# Sheet1.net
KiCad netlist of a schematic drawn in Altium Designer
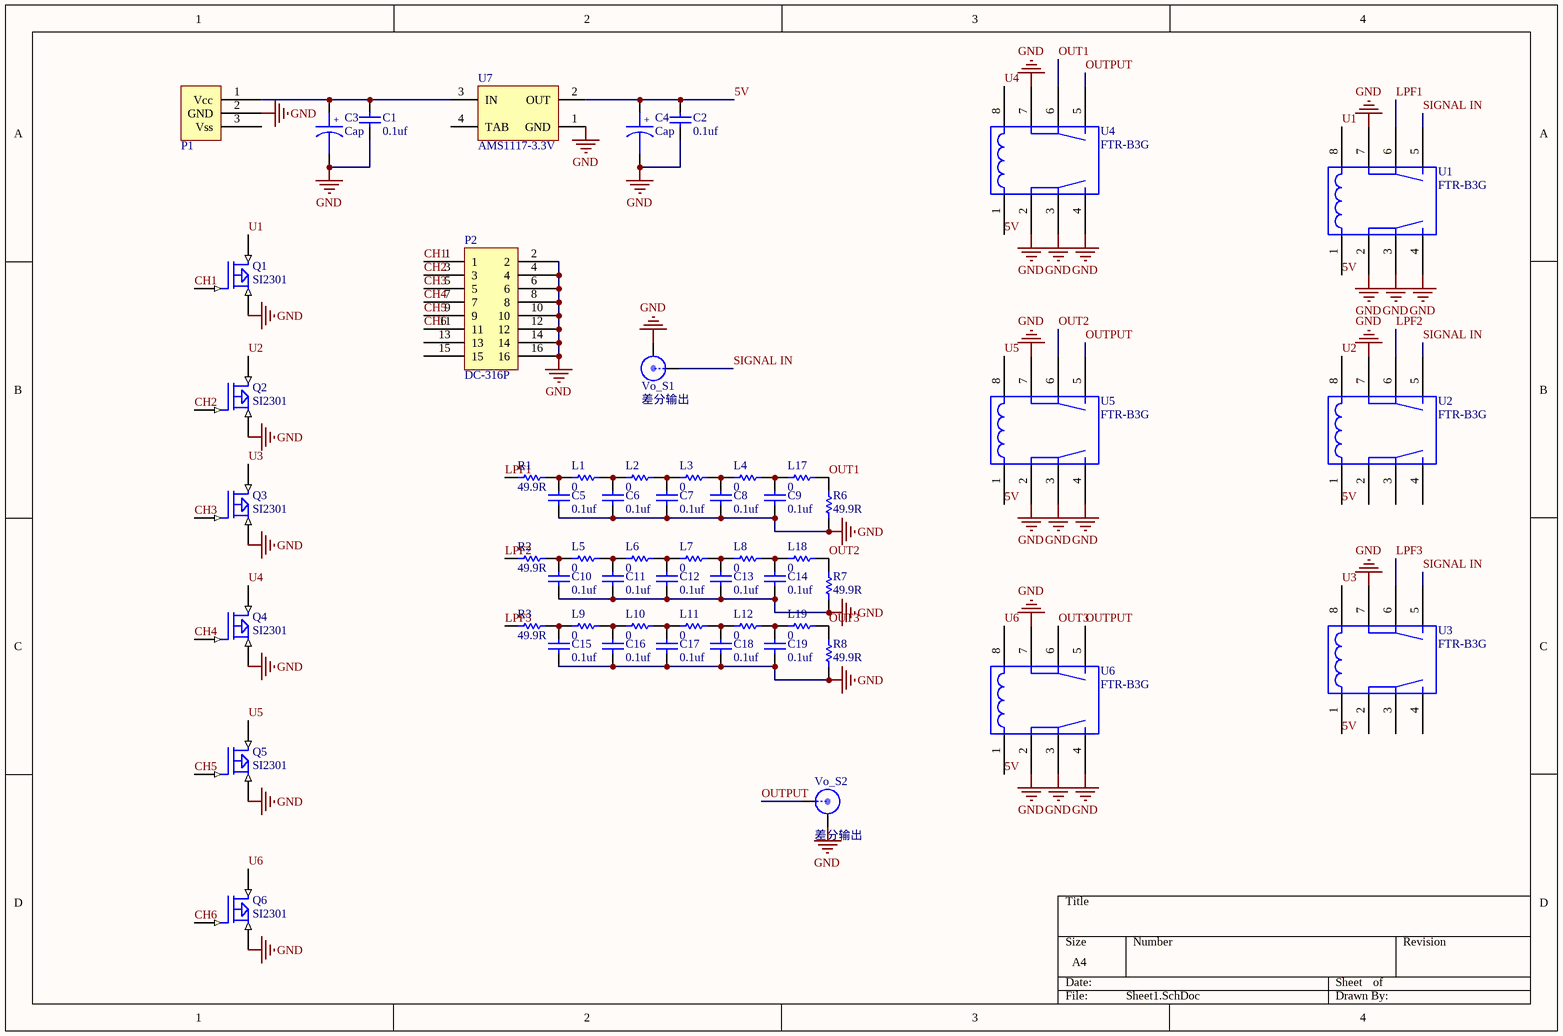
[diagram p0: Sheet1.SchDoc]

(export (version "E")
  (design (tool "Eeschema 10.0.6"))
  (components
    (comp (ref "C1") (value "0.1uf") (footprint "0805") (libsource (lib "Schlib1") (part "Cap")))
    (comp (ref "C2") (value "0.1uf") (footprint "0805") (libsource (lib "Schlib1") (part "Cap")))
    (comp (ref "C3")
      (value "Cap")
      (footprint "3216C-TYPE_A")
      (libsource (lib "Schlib1") (part "Tantalium Cap"))
    )
    (comp (ref "C4")
      (value "Cap")
      (footprint "3216C-TYPE_A")
      (libsource (lib "Schlib1") (part "Tantalium Cap"))
    )
    (comp (ref "C5") (value "0.1uf") (footprint "0603C") (libsource (lib "Schlib1") (part "Cap")))
    (comp (ref "C6") (value "0.1uf") (footprint "0603C") (libsource (lib "Schlib1") (part "Cap")))
    (comp (ref "C7") (value "0.1uf") (footprint "0603C") (libsource (lib "Schlib1") (part "Cap")))
    (comp (ref "C8") (value "0.1uf") (footprint "0603C") (libsource (lib "Schlib1") (part "Cap")))
    (comp (ref "C9") (value "0.1uf") (footprint "0603C") (libsource (lib "Schlib1") (part "Cap")))
    (comp (ref "C10") (value "0.1uf") (footprint "0603C") (libsource (lib "Schlib1") (part "Cap")))
    (comp (ref "C11") (value "0.1uf") (footprint "0603C") (libsource (lib "Schlib1") (part "Cap")))
    (comp (ref "C12") (value "0.1uf") (footprint "0603C") (libsource (lib "Schlib1") (part "Cap")))
    (comp (ref "C13") (value "0.1uf") (footprint "0603C") (libsource (lib "Schlib1") (part "Cap")))
    (comp (ref "C14") (value "0.1uf") (footprint "0603C") (libsource (lib "Schlib1") (part "Cap")))
    (comp (ref "C15") (value "0.1uf") (footprint "0603C") (libsource (lib "Schlib1") (part "Cap")))
    (comp (ref "C16") (value "0.1uf") (footprint "0603C") (libsource (lib "Schlib1") (part "Cap")))
    (comp (ref "C17") (value "0.1uf") (footprint "0603C") (libsource (lib "Schlib1") (part "Cap")))
    (comp (ref "C18") (value "0.1uf") (footprint "0603C") (libsource (lib "Schlib1") (part "Cap")))
    (comp (ref "C19") (value "0.1uf") (footprint "0603C") (libsource (lib "Schlib1") (part "Cap")))
    (comp (ref "L1") (value "0") (footprint "0603R") (libsource (lib "Schlib1") (part "Res")))
    (comp (ref "L2") (value "0") (footprint "0603R") (libsource (lib "Schlib1") (part "Res")))
    (comp (ref "L3") (value "0") (footprint "0603R") (libsource (lib "Schlib1") (part "Res")))
    (comp (ref "L4") (value "0") (footprint "0603R") (libsource (lib "Schlib1") (part "Res")))
    (comp (ref "L5") (value "0") (footprint "0603R") (libsource (lib "Schlib1") (part "Res")))
    (comp (ref "L6") (value "0") (footprint "0603R") (libsource (lib "Schlib1") (part "Res")))
    (comp (ref "L7") (value "0") (footprint "0603R") (libsource (lib "Schlib1") (part "Res")))
    (comp (ref "L8") (value "0") (footprint "0603R") (libsource (lib "Schlib1") (part "Res")))
    (comp (ref "L9") (value "0") (footprint "0603R") (libsource (lib "Schlib1") (part "Res")))
    (comp (ref "L10") (value "0") (footprint "0603R") (libsource (lib "Schlib1") (part "Res")))
    (comp (ref "L11") (value "0") (footprint "0603R") (libsource (lib "Schlib1") (part "Res")))
    (comp (ref "L12") (value "0") (footprint "0603R") (libsource (lib "Schlib1") (part "Res")))
    (comp (ref "L17") (value "0") (footprint "0603R") (libsource (lib "Schlib1") (part "Res")))
    (comp (ref "L18") (value "0") (footprint "0603R") (libsource (lib "Schlib1") (part "Res")))
    (comp (ref "L19") (value "0") (footprint "0603R") (libsource (lib "Schlib1") (part "Res")))
    (comp (ref "P1")
      (value "XH2.54-3p")
      (footprint "XH2.54-3p")
      (libsource (lib "Schlib1") (part "XH2.54-3p"))
    )
    (comp (ref "P2") (value "DC-316P") (footprint "DC3-14P") (libsource (lib "Schlib1") (part "DC3-16P")))
    (comp (ref "Q1") (value "SI2301") (footprint "SOT-23") (libsource (lib "Schlib1") (part "SI2301")))
    (comp (ref "Q2") (value "SI2301") (footprint "SOT-23") (libsource (lib "Schlib1") (part "SI2301")))
    (comp (ref "Q3") (value "SI2301") (footprint "SOT-23") (libsource (lib "Schlib1") (part "SI2301")))
    (comp (ref "Q4") (value "SI2301") (footprint "SOT-23") (libsource (lib "Schlib1") (part "SI2301")))
    (comp (ref "Q5") (value "SI2301") (footprint "SOT-23") (libsource (lib "Schlib1") (part "SI2301")))
    (comp (ref "Q6") (value "SI2301") (footprint "SOT-23") (libsource (lib "Schlib1") (part "SI2301")))
    (comp (ref "R1") (value "49.9R") (footprint "0603R") (libsource (lib "Schlib1") (part "Res")))
    (comp (ref "R2") (value "49.9R") (footprint "0603R") (libsource (lib "Schlib1") (part "Res")))
    (comp (ref "R3") (value "49.9R") (footprint "0603R") (libsource (lib "Schlib1") (part "Res")))
    (comp (ref "R6") (value "49.9R") (footprint "0603R") (libsource (lib "Schlib1") (part "Res")))
    (comp (ref "R7") (value "49.9R") (footprint "0603R") (libsource (lib "Schlib1") (part "Res")))
    (comp (ref "R8") (value "49.9R") (footprint "0603R") (libsource (lib "Schlib1") (part "Res")))
    (comp (ref "U1") (value "FTR-B3G") (footprint "FTR-B3G") (libsource (lib "Schlib1") (part "FTR-B3G")))
    (comp (ref "U2") (value "FTR-B3G") (footprint "FTR-B3G") (libsource (lib "Schlib1") (part "FTR-B3G")))
    (comp (ref "U3") (value "FTR-B3G") (footprint "FTR-B3G") (libsource (lib "Schlib1") (part "FTR-B3G")))
    (comp (ref "U4") (value "FTR-B3G") (footprint "FTR-B3G") (libsource (lib "Schlib1") (part "FTR-B3G")))
    (comp (ref "U5") (value "FTR-B3G") (footprint "FTR-B3G") (libsource (lib "Schlib1") (part "FTR-B3G")))
    (comp (ref "U6") (value "FTR-B3G") (footprint "FTR-B3G") (libsource (lib "Schlib1") (part "FTR-B3G")))
    (comp (ref "U7")
      (value "AMS1117-3.3V")
      (footprint "SOT-223")
      (libsource (lib "Schlib1") (part "AMS1117-3.3V"))
    )
    (comp (ref "Vo_S1") (value "差分输出") (footprint "SMA-LYING") (libsource (lib "Schlib1") (part "SMA")))
    (comp (ref "Vo_S2") (value "差分输出") (footprint "SMA-LYING") (libsource (lib "Schlib1") (part "SMA")))
  )
  (nets
    (net (code "1") (name "/5V") (class "Default")
      (node (ref "C2") (pin "2") (pinfunction "2_2") (pintype "passive"))
      (node (ref "C4") (pin "1") (pinfunction "1_1") (pintype "passive"))
      (node (ref "U1") (pin "1") (pinfunction "1_1") (pintype "passive"))
      (node (ref "U2") (pin "1") (pinfunction "1_1") (pintype "passive"))
      (node (ref "U3") (pin "1") (pinfunction "1_1") (pintype "passive"))
      (node (ref "U4") (pin "1") (pinfunction "1_1") (pintype "passive"))
      (node (ref "U5") (pin "1") (pinfunction "1_1") (pintype "passive"))
      (node (ref "U6") (pin "1") (pinfunction "1_1") (pintype "passive"))
      (node (ref "U7") (pin "2") (pinfunction "OUT_2") (pintype "power_in"))
    )
    (net (code "2") (name "/CH1") (class "Default")
      (node (ref "P2") (pin "1") (pinfunction "1_1") (pintype "passive"))
      (node (ref "Q1") (pin "1") (pinfunction "G_1") (pintype "input"))
    )
    (net (code "3") (name "/CH2") (class "Default")
      (node (ref "P2") (pin "3") (pinfunction "3_3") (pintype "passive"))
      (node (ref "Q2") (pin "1") (pinfunction "G_1") (pintype "input"))
    )
    (net (code "4") (name "/CH3") (class "Default")
      (node (ref "P2") (pin "5") (pinfunction "5_5") (pintype "passive"))
      (node (ref "Q3") (pin "1") (pinfunction "G_1") (pintype "input"))
    )
    (net (code "5") (name "/CH4") (class "Default")
      (node (ref "P2") (pin "7") (pinfunction "7_7") (pintype "passive"))
      (node (ref "Q4") (pin "1") (pinfunction "G_1") (pintype "input"))
    )
    (net (code "6") (name "/CH5") (class "Default")
      (node (ref "P2") (pin "9") (pinfunction "9_9") (pintype "passive"))
      (node (ref "Q5") (pin "1") (pinfunction "G_1") (pintype "input"))
    )
    (net (code "7") (name "/CH6") (class "Default")
      (node (ref "P2") (pin "11") (pinfunction "11_11") (pintype "passive"))
      (node (ref "Q6") (pin "1") (pinfunction "G_1") (pintype "input"))
    )
    (net (code "8") (name "/LPF1") (class "Default")
      (node (ref "R1") (pin "1") (pinfunction "1_1") (pintype "passive"))
      (node (ref "U1") (pin "6") (pinfunction "6_6") (pintype "passive"))
    )
    (net (code "9") (name "/LPF2") (class "Default")
      (node (ref "R2") (pin "1") (pinfunction "1_1") (pintype "passive"))
      (node (ref "U2") (pin "6") (pinfunction "6_6") (pintype "passive"))
    )
    (net (code "10") (name "/LPF3") (class "Default")
      (node (ref "R3") (pin "1") (pinfunction "1_1") (pintype "passive"))
      (node (ref "U3") (pin "6") (pinfunction "6_6") (pintype "passive"))
    )
    (net (code "11") (name "/OUT1") (class "Default")
      (node (ref "L17") (pin "2") (pinfunction "2_2") (pintype "passive"))
      (node (ref "R6") (pin "2") (pinfunction "2_2") (pintype "passive"))
      (node (ref "U4") (pin "6") (pinfunction "6_6") (pintype "passive"))
    )
    (net (code "12") (name "/OUT2") (class "Default")
      (node (ref "L18") (pin "2") (pinfunction "2_2") (pintype "passive"))
      (node (ref "R7") (pin "2") (pinfunction "2_2") (pintype "passive"))
      (node (ref "U5") (pin "6") (pinfunction "6_6") (pintype "passive"))
    )
    (net (code "13") (name "/OUT3") (class "Default")
      (node (ref "L19") (pin "2") (pinfunction "2_2") (pintype "passive"))
      (node (ref "R8") (pin "2") (pinfunction "2_2") (pintype "passive"))
      (node (ref "U6") (pin "6") (pinfunction "6_6") (pintype "passive"))
    )
    (net (code "14") (name "/OUTPUT") (class "Default")
      (node (ref "U4") (pin "5") (pinfunction "5_5") (pintype "passive"))
      (node (ref "U5") (pin "5") (pinfunction "5_5") (pintype "passive"))
      (node (ref "U6") (pin "5") (pinfunction "5_5") (pintype "passive"))
      (node (ref "Vo_S2") (pin "0") (pinfunction "0_0") (pintype "passive"))
    )
    (net (code "15") (name "/SIGNAL IN") (class "Default")
      (node (ref "U1") (pin "5") (pinfunction "5_5") (pintype "passive"))
      (node (ref "U2") (pin "5") (pinfunction "5_5") (pintype "passive"))
      (node (ref "U3") (pin "5") (pinfunction "5_5") (pintype "passive"))
      (node (ref "Vo_S1") (pin "0") (pinfunction "0_0") (pintype "passive"))
    )
    (net (code "16") (name "/U1") (class "Default")
      (node (ref "Q1") (pin "2") (pinfunction "S_2") (pintype "input"))
      (node (ref "U1") (pin "8") (pinfunction "8_8") (pintype "passive"))
    )
    (net (code "17") (name "/U2") (class "Default")
      (node (ref "Q2") (pin "2") (pinfunction "S_2") (pintype "input"))
      (node (ref "U2") (pin "8") (pinfunction "8_8") (pintype "passive"))
    )
    (net (code "18") (name "/U3") (class "Default")
      (node (ref "Q3") (pin "2") (pinfunction "S_2") (pintype "input"))
      (node (ref "U3") (pin "8") (pinfunction "8_8") (pintype "passive"))
    )
    (net (code "19") (name "/U4") (class "Default")
      (node (ref "Q4") (pin "2") (pinfunction "S_2") (pintype "input"))
      (node (ref "U4") (pin "8") (pinfunction "8_8") (pintype "passive"))
    )
    (net (code "20") (name "/U5") (class "Default")
      (node (ref "Q5") (pin "2") (pinfunction "S_2") (pintype "input"))
      (node (ref "U5") (pin "8") (pinfunction "8_8") (pintype "passive"))
    )
    (net (code "21") (name "/U6") (class "Default")
      (node (ref "Q6") (pin "2") (pinfunction "S_2") (pintype "input"))
      (node (ref "U6") (pin "8") (pinfunction "8_8") (pintype "passive"))
    )
    (net (code "22") (name "GND") (class "Default")
      (node (ref "C1") (pin "1") (pinfunction "1_1") (pintype "passive"))
      (node (ref "C10") (pin "1") (pinfunction "1_1") (pintype "passive"))
      (node (ref "C11") (pin "1") (pinfunction "1_1") (pintype "passive"))
      (node (ref "C12") (pin "1") (pinfunction "1_1") (pintype "passive"))
      (node (ref "C13") (pin "1") (pinfunction "1_1") (pintype "passive"))
      (node (ref "C14") (pin "1") (pinfunction "1_1") (pintype "passive"))
      (node (ref "C15") (pin "1") (pinfunction "1_1") (pintype "passive"))
      (node (ref "C16") (pin "1") (pinfunction "1_1") (pintype "passive"))
      (node (ref "C17") (pin "1") (pinfunction "1_1") (pintype "passive"))
      (node (ref "C18") (pin "1") (pinfunction "1_1") (pintype "passive"))
      (node (ref "C19") (pin "1") (pinfunction "1_1") (pintype "passive"))
      (node (ref "C2") (pin "1") (pinfunction "1_1") (pintype "passive"))
      (node (ref "C3") (pin "2") (pinfunction "2_2") (pintype "passive"))
      (node (ref "C4") (pin "2") (pinfunction "2_2") (pintype "passive"))
      (node (ref "C5") (pin "1") (pinfunction "1_1") (pintype "passive"))
      (node (ref "C6") (pin "1") (pinfunction "1_1") (pintype "passive"))
      (node (ref "C7") (pin "1") (pinfunction "1_1") (pintype "passive"))
      (node (ref "C8") (pin "1") (pinfunction "1_1") (pintype "passive"))
      (node (ref "C9") (pin "1") (pinfunction "1_1") (pintype "passive"))
      (node (ref "P1") (pin "2") (pinfunction "GND_2") (pintype "passive"))
      (node (ref "P2") (pin "10") (pinfunction "10_10") (pintype "passive"))
      (node (ref "P2") (pin "12") (pinfunction "12_12") (pintype "passive"))
      (node (ref "P2") (pin "14") (pinfunction "14_14") (pintype "passive"))
      (node (ref "P2") (pin "16") (pinfunction "16_16") (pintype "passive"))
      (node (ref "P2") (pin "2") (pinfunction "2_2") (pintype "passive"))
      (node (ref "P2") (pin "4") (pinfunction "4_4") (pintype "passive"))
      (node (ref "P2") (pin "6") (pinfunction "6_6") (pintype "passive"))
      (node (ref "P2") (pin "8") (pinfunction "8_8") (pintype "passive"))
      (node (ref "Q1") (pin "3") (pinfunction "D_3") (pintype "input"))
      (node (ref "Q2") (pin "3") (pinfunction "D_3") (pintype "input"))
      (node (ref "Q3") (pin "3") (pinfunction "D_3") (pintype "input"))
      (node (ref "Q4") (pin "3") (pinfunction "D_3") (pintype "input"))
      (node (ref "Q5") (pin "3") (pinfunction "D_3") (pintype "input"))
      (node (ref "Q6") (pin "3") (pinfunction "D_3") (pintype "input"))
      (node (ref "R6") (pin "1") (pinfunction "1_1") (pintype "passive"))
      (node (ref "R7") (pin "1") (pinfunction "1_1") (pintype "passive"))
      (node (ref "R8") (pin "1") (pinfunction "1_1") (pintype "passive"))
      (node (ref "U1") (pin "2") (pinfunction "2_2") (pintype "passive"))
      (node (ref "U1") (pin "3") (pinfunction "3_3") (pintype "passive"))
      (node (ref "U1") (pin "4") (pinfunction "4_4") (pintype "passive"))
      (node (ref "U1") (pin "7") (pinfunction "7_7") (pintype "passive"))
      (node (ref "U2") (pin "7") (pinfunction "7_7") (pintype "passive"))
      (node (ref "U3") (pin "7") (pinfunction "7_7") (pintype "passive"))
      (node (ref "U4") (pin "2") (pinfunction "2_2") (pintype "passive"))
      (node (ref "U4") (pin "3") (pinfunction "3_3") (pintype "passive"))
      (node (ref "U4") (pin "4") (pinfunction "4_4") (pintype "passive"))
      (node (ref "U4") (pin "7") (pinfunction "7_7") (pintype "passive"))
      (node (ref "U5") (pin "2") (pinfunction "2_2") (pintype "passive"))
      (node (ref "U5") (pin "3") (pinfunction "3_3") (pintype "passive"))
      (node (ref "U5") (pin "4") (pinfunction "4_4") (pintype "passive"))
      (node (ref "U5") (pin "7") (pinfunction "7_7") (pintype "passive"))
      (node (ref "U6") (pin "2") (pinfunction "2_2") (pintype "passive"))
      (node (ref "U6") (pin "3") (pinfunction "3_3") (pintype "passive"))
      (node (ref "U6") (pin "4") (pinfunction "4_4") (pintype "passive"))
      (node (ref "U6") (pin "7") (pinfunction "7_7") (pintype "passive"))
      (node (ref "U7") (pin "1") (pinfunction "GND_1") (pintype "power_in"))
      (node (ref "Vo_S1") (pin "1") (pinfunction "1_1") (pintype "passive"))
      (node (ref "Vo_S2") (pin "1") (pinfunction "1_1") (pintype "passive"))
    )
    (net (code "23") (name "Net-(C5-Pad2)") (class "Default")
      (node (ref "C5") (pin "2") (pinfunction "2_2") (pintype "passive"))
      (node (ref "L1") (pin "1") (pinfunction "1_1") (pintype "passive"))
      (node (ref "R1") (pin "2") (pinfunction "2_2") (pintype "passive"))
    )
    (net (code "24") (name "Net-(C6-Pad2)") (class "Default")
      (node (ref "C6") (pin "2") (pinfunction "2_2") (pintype "passive"))
      (node (ref "L1") (pin "2") (pinfunction "2_2") (pintype "passive"))
      (node (ref "L2") (pin "1") (pinfunction "1_1") (pintype "passive"))
    )
    (net (code "25") (name "Net-(C7-Pad2)") (class "Default")
      (node (ref "C7") (pin "2") (pinfunction "2_2") (pintype "passive"))
      (node (ref "L2") (pin "2") (pinfunction "2_2") (pintype "passive"))
      (node (ref "L3") (pin "1") (pinfunction "1_1") (pintype "passive"))
    )
    (net (code "26") (name "Net-(C8-Pad2)") (class "Default")
      (node (ref "C8") (pin "2") (pinfunction "2_2") (pintype "passive"))
      (node (ref "L3") (pin "2") (pinfunction "2_2") (pintype "passive"))
      (node (ref "L4") (pin "1") (pinfunction "1_1") (pintype "passive"))
    )
    (net (code "27") (name "Net-(C9-Pad2)") (class "Default")
      (node (ref "C9") (pin "2") (pinfunction "2_2") (pintype "passive"))
      (node (ref "L17") (pin "1") (pinfunction "1_1") (pintype "passive"))
      (node (ref "L4") (pin "2") (pinfunction "2_2") (pintype "passive"))
    )
    (net (code "28") (name "Net-(C10-Pad2)") (class "Default")
      (node (ref "C10") (pin "2") (pinfunction "2_2") (pintype "passive"))
      (node (ref "L5") (pin "1") (pinfunction "1_1") (pintype "passive"))
      (node (ref "R2") (pin "2") (pinfunction "2_2") (pintype "passive"))
    )
    (net (code "29") (name "Net-(C11-Pad2)") (class "Default")
      (node (ref "C11") (pin "2") (pinfunction "2_2") (pintype "passive"))
      (node (ref "L5") (pin "2") (pinfunction "2_2") (pintype "passive"))
      (node (ref "L6") (pin "1") (pinfunction "1_1") (pintype "passive"))
    )
    (net (code "30") (name "Net-(C12-Pad2)") (class "Default")
      (node (ref "C12") (pin "2") (pinfunction "2_2") (pintype "passive"))
      (node (ref "L6") (pin "2") (pinfunction "2_2") (pintype "passive"))
      (node (ref "L7") (pin "1") (pinfunction "1_1") (pintype "passive"))
    )
    (net (code "31") (name "Net-(C13-Pad2)") (class "Default")
      (node (ref "C13") (pin "2") (pinfunction "2_2") (pintype "passive"))
      (node (ref "L7") (pin "2") (pinfunction "2_2") (pintype "passive"))
      (node (ref "L8") (pin "1") (pinfunction "1_1") (pintype "passive"))
    )
    (net (code "32") (name "Net-(C14-Pad2)") (class "Default")
      (node (ref "C14") (pin "2") (pinfunction "2_2") (pintype "passive"))
      (node (ref "L18") (pin "1") (pinfunction "1_1") (pintype "passive"))
      (node (ref "L8") (pin "2") (pinfunction "2_2") (pintype "passive"))
    )
    (net (code "33") (name "Net-(C15-Pad2)") (class "Default")
      (node (ref "C15") (pin "2") (pinfunction "2_2") (pintype "passive"))
      (node (ref "L9") (pin "1") (pinfunction "1_1") (pintype "passive"))
      (node (ref "R3") (pin "2") (pinfunction "2_2") (pintype "passive"))
    )
    (net (code "34") (name "Net-(C16-Pad2)") (class "Default")
      (node (ref "C16") (pin "2") (pinfunction "2_2") (pintype "passive"))
      (node (ref "L10") (pin "1") (pinfunction "1_1") (pintype "passive"))
      (node (ref "L9") (pin "2") (pinfunction "2_2") (pintype "passive"))
    )
    (net (code "35") (name "Net-(C17-Pad2)") (class "Default")
      (node (ref "C17") (pin "2") (pinfunction "2_2") (pintype "passive"))
      (node (ref "L10") (pin "2") (pinfunction "2_2") (pintype "passive"))
      (node (ref "L11") (pin "1") (pinfunction "1_1") (pintype "passive"))
    )
    (net (code "36") (name "Net-(C18-Pad2)") (class "Default")
      (node (ref "C18") (pin "2") (pinfunction "2_2") (pintype "passive"))
      (node (ref "L11") (pin "2") (pinfunction "2_2") (pintype "passive"))
      (node (ref "L12") (pin "1") (pinfunction "1_1") (pintype "passive"))
    )
    (net (code "37") (name "Net-(C19-Pad2)") (class "Default")
      (node (ref "C19") (pin "2") (pinfunction "2_2") (pintype "passive"))
      (node (ref "L12") (pin "2") (pinfunction "2_2") (pintype "passive"))
      (node (ref "L19") (pin "1") (pinfunction "1_1") (pintype "passive"))
    )
    (net (code "38") (name "Net-(P1-Vcc)") (class "Default")
      (node (ref "C1") (pin "2") (pinfunction "2_2") (pintype "passive"))
      (node (ref "C3") (pin "1") (pinfunction "1_1") (pintype "passive"))
      (node (ref "P1") (pin "1") (pinfunction "Vcc_1") (pintype "passive"))
      (node (ref "U7") (pin "3") (pinfunction "IN_3") (pintype "power_in"))
    )
    (net (code "39") (name "unconnected-(P1-Vss-Pad3)") (class "Default")
      (node (ref "P1") (pin "3") (pinfunction "Vss_3") (pintype "passive"))
    )
    (net (code "40") (name "unconnected-(P2-Pad13)") (class "Default")
      (node (ref "P2") (pin "13") (pinfunction "13_13") (pintype "passive"))
    )
    (net (code "41") (name "unconnected-(P2-Pad15)") (class "Default")
      (node (ref "P2") (pin "15") (pinfunction "15_15") (pintype "passive"))
    )
    (net (code "42") (name "unconnected-(U2-Pad2)") (class "Default")
      (node (ref "U2") (pin "2") (pinfunction "2_2") (pintype "passive"))
    )
    (net (code "43") (name "unconnected-(U2-Pad3)") (class "Default")
      (node (ref "U2") (pin "3") (pinfunction "3_3") (pintype "passive"))
    )
    (net (code "44") (name "unconnected-(U2-Pad4)") (class "Default")
      (node (ref "U2") (pin "4") (pinfunction "4_4") (pintype "passive"))
    )
    (net (code "45") (name "unconnected-(U3-Pad2)") (class "Default")
      (node (ref "U3") (pin "2") (pinfunction "2_2") (pintype "passive"))
    )
    (net (code "46") (name "unconnected-(U3-Pad3)") (class "Default")
      (node (ref "U3") (pin "3") (pinfunction "3_3") (pintype "passive"))
    )
    (net (code "47") (name "unconnected-(U3-Pad4)") (class "Default")
      (node (ref "U3") (pin "4") (pinfunction "4_4") (pintype "passive"))
    )
    (net (code "48") (name "unconnected-(U7-TAB-Pad4)") (class "Default")
      (node (ref "U7") (pin "4") (pinfunction "TAB_4") (pintype "power_in"))
    )
  )
)
